# I2C_Keypad.net
KiCad netlist of a schematic drawn in Altium Designer
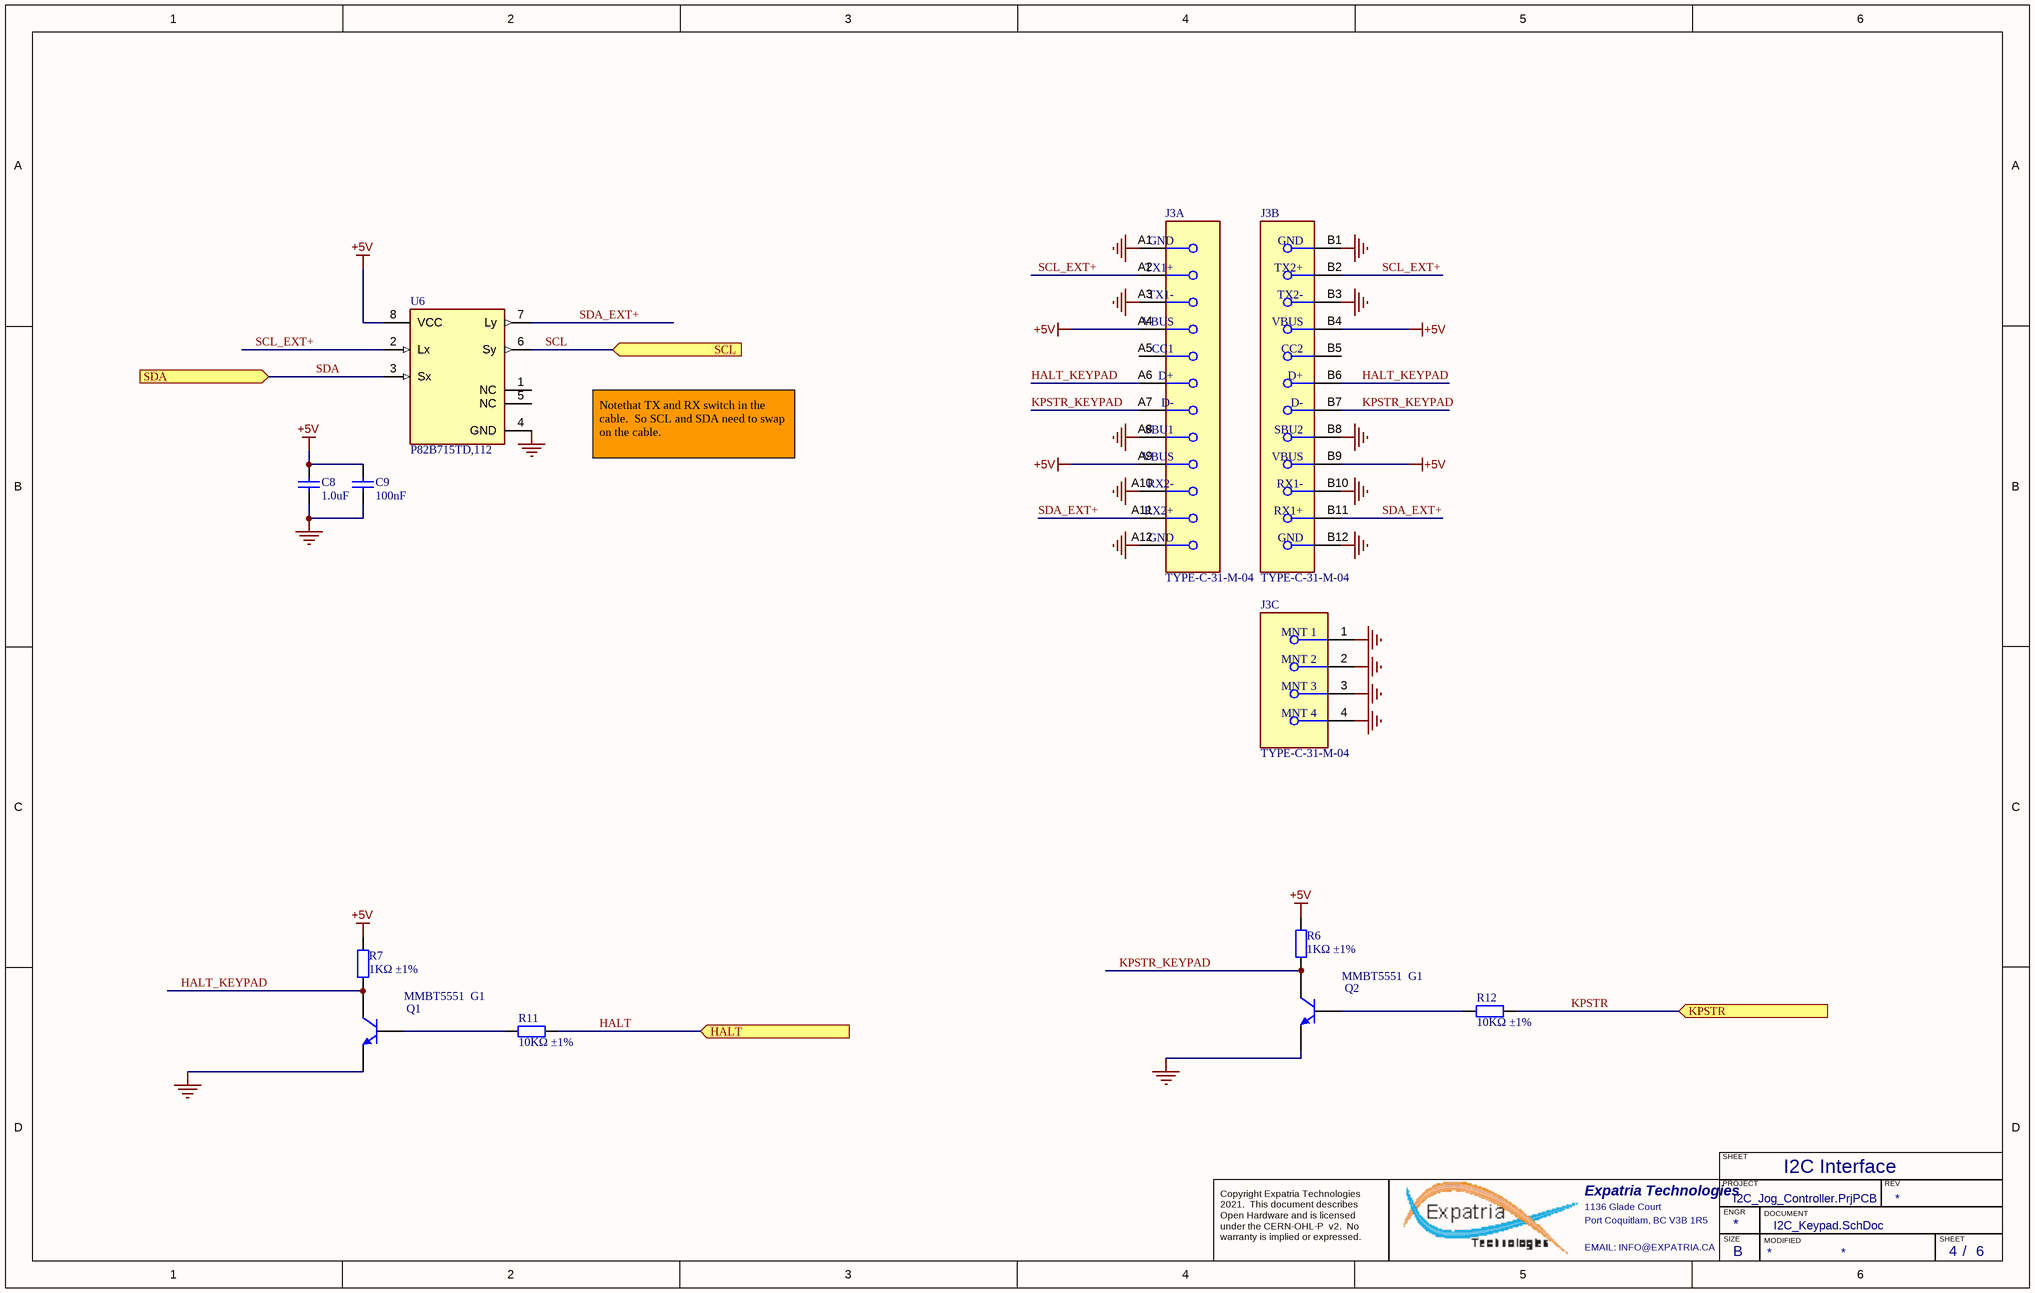
[diagram p0: I2C_Keypad.SchDoc]

(export (version "E")
  (design (tool "Eeschema 10.0.6"))
  (components
    (comp (ref "C8")
      (value "1.0uF")
      (footprint "0402_C")
      (description "Chip capacitor")
      (fields
        (field (name "MANUFACTURER") "Samsung Electro-Mechanics")
        (field (name "PARTNUMBER") "CL05A105KA5NQNC")
      )
      (libsource (lib "Cap") (part "0402 1.0uF (105) 10% 25V"))
    )
    (comp (ref "C9")
      (value "100nF")
      (footprint "0402_C")
      (description "Chip capacitors")
      (fields
        (field (name "MANUFACTURER") "Samsung Electro-Mechanics")
        (field (name "PARTNUMBER") "CL05B104KO5NNNC")
      )
      (libsource (lib "Cap") (part "0402 100nF (104) 10% 16V"))
    )
    (comp (ref "J3")
      (value "TYPE-C-31-M-04")
      (footprint "USB-C-SMD_TYPE-C-USB-20")
      (description "CONN RCP USB3.1 TYPEC 24P SMD RA")
      (fields (field (name "MANUFACTURER") "Korean Hroparts Elec"))
      (libsource (lib "") (part "USBC TYPE-C-31-M-04_1"))
    )
    (comp (ref "Q1")
      (value "MMBT5551  G1")
      (footprint "SOT-23(SOT-23-3)")
      (description "三极管")
      (libsource (lib "Transistor_NPN") (part "SOT-23 MMBT5551  G1"))
    )
    (comp (ref "Q2")
      (value "MMBT5551  G1")
      (footprint "SOT-23(SOT-23-3)")
      (description "三极管")
      (libsource (lib "Transistor_NPN") (part "SOT-23 MMBT5551  G1"))
    )
    (comp (ref "R6")
      (value "1KΩ ±1%")
      (footprint "0402_R")
      (description "Chip resistor")
      (fields (field (name "MANUFACTURER") "Uniroyal Elec") (field (name "PARTNUMBER") "0402WGF1001TCE"))
      (libsource (lib "RES") (part "0402 1K (1001) 1%"))
    )
    (comp (ref "R7")
      (value "1KΩ ±1%")
      (footprint "0402_R")
      (description "Chip resistor")
      (fields (field (name "MANUFACTURER") "Uniroyal Elec") (field (name "PARTNUMBER") "0402WGF1001TCE"))
      (libsource (lib "RES") (part "0402 1K (1001) 1%"))
    )
    (comp (ref "R11")
      (value "10KΩ ±1%")
      (footprint "0402_R")
      (description "Chip resistor")
      (fields (field (name "MANUFACTURER") "Uniroyal Elec") (field (name "PARTNUMBER") "0402WGF1002TCE"))
      (libsource (lib "RES") (part "0402 10K (1002) 1%"))
    )
    (comp (ref "R12")
      (value "10KΩ ±1%")
      (footprint "0402_R")
      (description "Chip resistor")
      (fields (field (name "MANUFACTURER") "Uniroyal Elec") (field (name "PARTNUMBER") "0402WGF1002TCE"))
      (libsource (lib "") (part "0402 10K (1002) 1%_1"))
    )
    (comp (ref "U6")
      (value "P82B715TD,112")
      (footprint "FP-SOT96-1-MFG")
      (description "IC REDRIVER I2C 1CH 400KHZ 8SO")
      (fields
        (field (name "MANUFACTURER") "NXP Semicon")
        (field (name "MANUFACTURER_PART_NUMBER") "P82B715TD,118")
      )
      (libsource (lib "Altium Content Vault") (part "feec727f4072afc4f94d4e12e138974"))
    )
  )
  (nets
    (net (code "1") (name "+5V") (class "Default")
      (node (ref "C8") (pin "2") (pinfunction "2_2") (pintype "passive"))
      (node (ref "C9") (pin "2") (pinfunction "2_2") (pintype "passive"))
      (node (ref "J3") (pin "A4") (pinfunction "VBUS_A4") (pintype "passive"))
      (node (ref "J3") (pin "A9") (pinfunction "VBUS_A9") (pintype "passive"))
      (node (ref "J3") (pin "B4") (pinfunction "VBUS_B4") (pintype "passive"))
      (node (ref "J3") (pin "B9") (pinfunction "VBUS_B9") (pintype "passive"))
      (node (ref "R6") (pin "1") (pinfunction "1_1") (pintype "passive"))
      (node (ref "R7") (pin "1") (pinfunction "1_1") (pintype "passive"))
      (node (ref "U6") (pin "8") (pinfunction "VCC_8") (pintype "power_in"))
    )
    (net (code "2") (name "/HALT") (class "Default")
      (node (ref "R11") (pin "2") (pinfunction "2_2") (pintype "passive"))
    )
    (net (code "3") (name "/HALT_KEYPAD") (class "Default")
      (node (ref "J3") (pin "A6") (pinfunction "D+_A6") (pintype "passive"))
      (node (ref "J3") (pin "B6") (pinfunction "D+_B6") (pintype "passive"))
      (node (ref "Q1") (pin "3") (pinfunction "C_3") (pintype "passive"))
      (node (ref "R7") (pin "2") (pinfunction "2_2") (pintype "passive"))
    )
    (net (code "4") (name "/KPSTR") (class "Default")
      (node (ref "R12") (pin "1") (pinfunction "1_1") (pintype "passive"))
    )
    (net (code "5") (name "/KPSTR_KEYPAD") (class "Default")
      (node (ref "J3") (pin "A7") (pinfunction "D-_A7") (pintype "passive"))
      (node (ref "J3") (pin "B7") (pinfunction "D-_B7") (pintype "passive"))
      (node (ref "Q2") (pin "3") (pinfunction "C_3") (pintype "passive"))
      (node (ref "R6") (pin "2") (pinfunction "2_2") (pintype "passive"))
    )
    (net (code "6") (name "/SCL") (class "Default")
      (node (ref "U6") (pin "6") (pinfunction "Sy_6") (pintype "output"))
    )
    (net (code "7") (name "/SCL_EXT+") (class "Default")
      (node (ref "J3") (pin "A2") (pinfunction "TX1+_A2") (pintype "passive"))
      (node (ref "J3") (pin "B2") (pinfunction "TX2+_B2") (pintype "passive"))
      (node (ref "U6") (pin "2") (pinfunction "Lx_2") (pintype "input"))
    )
    (net (code "8") (name "/SDA") (class "Default")
      (node (ref "U6") (pin "3") (pinfunction "Sx_3") (pintype "input"))
    )
    (net (code "9") (name "/SDA_EXT+") (class "Default")
      (node (ref "J3") (pin "A11") (pinfunction "RX2+_A11") (pintype "passive"))
      (node (ref "J3") (pin "B11") (pinfunction "RX1+_B11") (pintype "passive"))
      (node (ref "U6") (pin "7") (pinfunction "Ly_7") (pintype "output"))
    )
    (net (code "10") (name "GND") (class "Default")
      (node (ref "C8") (pin "1") (pinfunction "1_1") (pintype "passive"))
      (node (ref "C9") (pin "1") (pinfunction "1_1") (pintype "passive"))
      (node (ref "J3") (pin "1") (pinfunction "MNT_1_1") (pintype "passive"))
      (node (ref "J3") (pin "2") (pinfunction "MNT_2_2") (pintype "passive"))
      (node (ref "J3") (pin "3") (pinfunction "MNT_3_3") (pintype "passive"))
      (node (ref "J3") (pin "4") (pinfunction "MNT_4_4") (pintype "passive"))
      (node (ref "J3") (pin "A1") (pinfunction "GND_A1") (pintype "passive"))
      (node (ref "J3") (pin "A10") (pinfunction "RX2-_A10") (pintype "passive"))
      (node (ref "J3") (pin "A12") (pinfunction "GND_A12") (pintype "passive"))
      (node (ref "J3") (pin "A3") (pinfunction "TX1-_A3") (pintype "passive"))
      (node (ref "J3") (pin "A8") (pinfunction "SBU1_A8") (pintype "passive"))
      (node (ref "J3") (pin "B1") (pinfunction "GND_B1") (pintype "passive"))
      (node (ref "J3") (pin "B10") (pinfunction "RX1-_B10") (pintype "passive"))
      (node (ref "J3") (pin "B12") (pinfunction "GND_B12") (pintype "passive"))
      (node (ref "J3") (pin "B3") (pinfunction "TX2-_B3") (pintype "passive"))
      (node (ref "J3") (pin "B8") (pinfunction "SBU2_B8") (pintype "passive"))
      (node (ref "Q1") (pin "2") (pinfunction "E_2") (pintype "passive"))
      (node (ref "Q2") (pin "2") (pinfunction "E_2") (pintype "passive"))
      (node (ref "U6") (pin "4") (pinfunction "GND_4") (pintype "power_in"))
    )
    (net (code "11") (name "Net-(Q1-B)") (class "Default")
      (node (ref "Q1") (pin "1") (pinfunction "B_1") (pintype "passive"))
      (node (ref "R11") (pin "1") (pinfunction "1_1") (pintype "passive"))
    )
    (net (code "12") (name "Net-(Q2-B)") (class "Default")
      (node (ref "Q2") (pin "1") (pinfunction "B_1") (pintype "passive"))
      (node (ref "R12") (pin "2") (pinfunction "2_2") (pintype "passive"))
    )
    (net (code "13") (name "unconnected-(J3A-CC1-PadA5)") (class "Default")
      (node (ref "J3") (pin "A5") (pinfunction "CC1_A5") (pintype "passive"))
    )
    (net (code "14") (name "unconnected-(J3B-CC2-PadB5)") (class "Default")
      (node (ref "J3") (pin "B5") (pinfunction "CC2_B5") (pintype "passive"))
    )
    (net (code "15") (name "unconnected-(U6-NC-Pad1)") (class "Default")
      (node (ref "U6") (pin "1") (pinfunction "NC_1") (pintype "passive"))
    )
    (net (code "16") (name "unconnected-(U6-NC-Pad5)") (class "Default")
      (node (ref "U6") (pin "5") (pinfunction "NC_5") (pintype "passive"))
    )
  )
)
